# DSO_RAM.net
KiCad netlist of a schematic drawn in Altium Designer
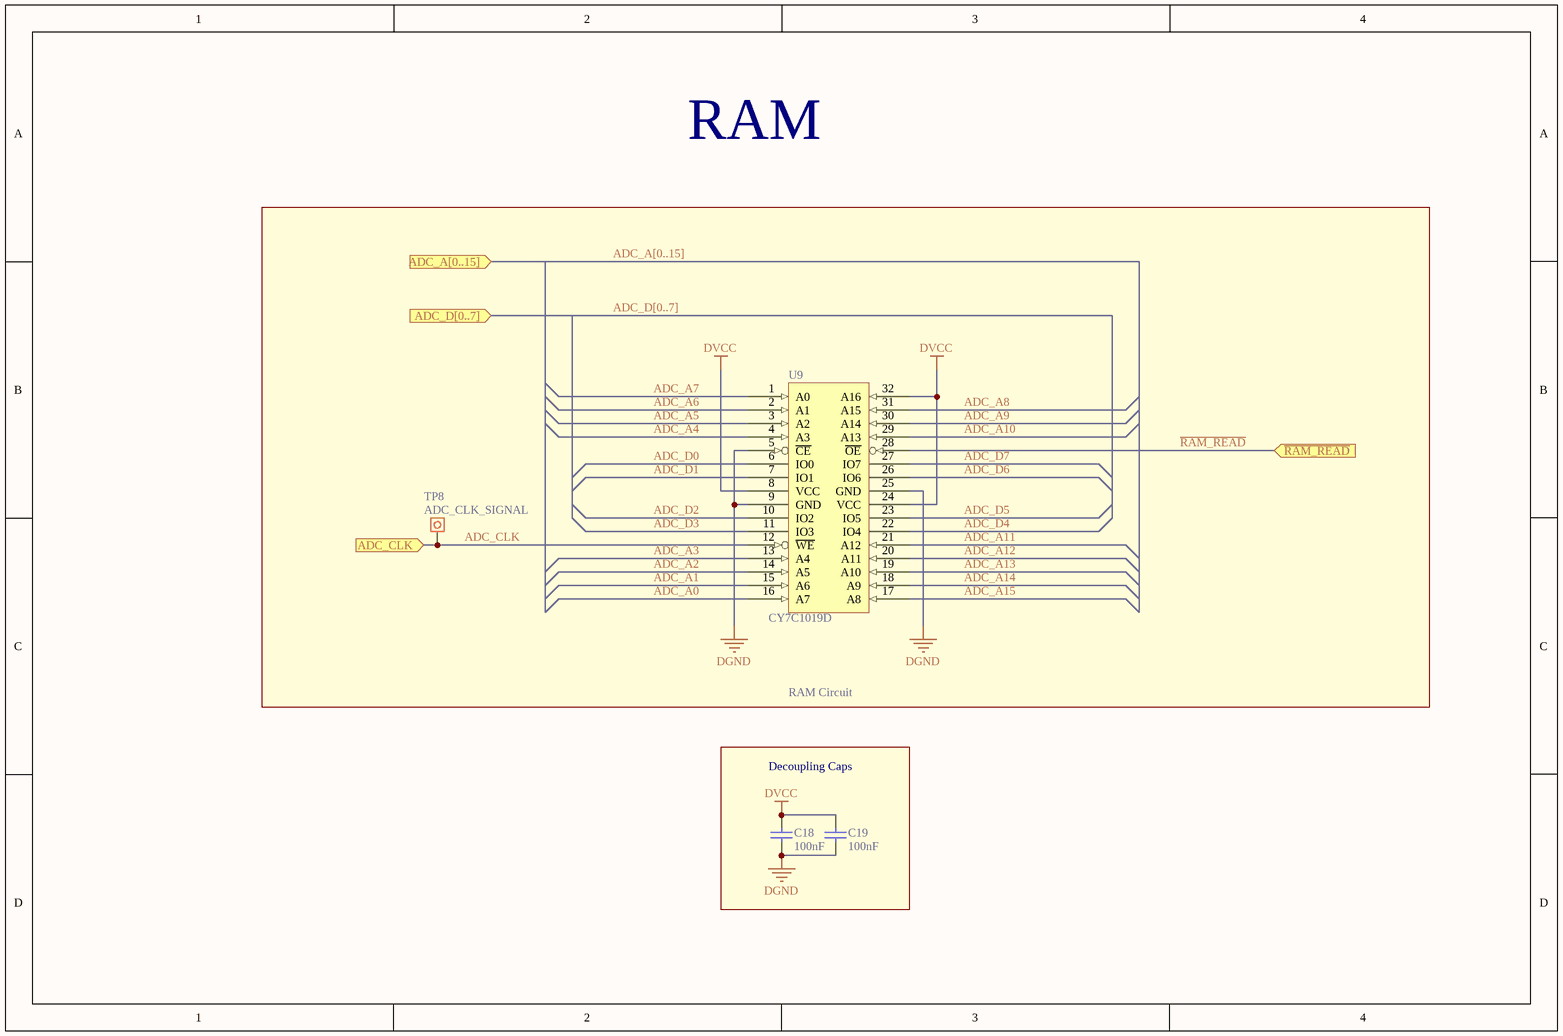
[diagram p0: DSO_RAM.SchDoc]

(export (version "E")
  (design (tool "Eeschema 10.0.6"))
  (components
    (comp (ref "C18")
      (value "100nF")
      (footprint "0805C")
      (description "Capacitor")
      (fields (field (name "REVIEWED BY") "RM - 2018/08/05"))
      (libsource (lib "DSO") (part "C"))
    )
    (comp (ref "C19")
      (value "100nF")
      (footprint "0805C")
      (description "Capacitor")
      (fields (field (name "REVIEWED BY") "RM - 2018/08/05"))
      (libsource (lib "DSO") (part "C"))
    )
    (comp (ref "TP8")
      (value "ADC_CLK_SIGNAL")
      (footprint "Testpoin")
      (description "Pad")
      (fields (field (name "Comment") "INPUT"))
      (libsource (lib "DSO") (part "Test Point"))
    )
    (comp (ref "U9")
      (value "CY7C1019D")
      (footprint "TSOP-32")
      (description "SRAM 128k x 8")
      (fields (field (name "REVIEWED BY") "RM - 2018/08/05"))
      (libsource (lib "DSO") (part "CY7C1019D"))
    )
  )
  (nets
    (net (code "1") (name "/ADC_A0") (class "Default")
      (node (ref "U9") (pin "16") (pinfunction "A7_16") (pintype "input"))
    )
    (net (code "2") (name "/ADC_A1") (class "Default")
      (node (ref "U9") (pin "15") (pinfunction "A6_15") (pintype "input"))
    )
    (net (code "3") (name "/ADC_A2") (class "Default")
      (node (ref "U9") (pin "14") (pinfunction "A5_14") (pintype "input"))
    )
    (net (code "4") (name "/ADC_A3") (class "Default")
      (node (ref "U9") (pin "13") (pinfunction "A4_13") (pintype "input"))
    )
    (net (code "5") (name "/ADC_A4") (class "Default")
      (node (ref "U9") (pin "4") (pinfunction "A3_4") (pintype "input"))
    )
    (net (code "6") (name "/ADC_A5") (class "Default")
      (node (ref "U9") (pin "3") (pinfunction "A2_3") (pintype "input"))
    )
    (net (code "7") (name "/ADC_A6") (class "Default")
      (node (ref "U9") (pin "2") (pinfunction "A1_2") (pintype "input"))
    )
    (net (code "8") (name "/ADC_A7") (class "Default")
      (node (ref "U9") (pin "1") (pinfunction "A0_1") (pintype "input"))
    )
    (net (code "9") (name "/ADC_A8") (class "Default")
      (node (ref "U9") (pin "31") (pinfunction "A15_31") (pintype "input"))
    )
    (net (code "10") (name "/ADC_A9") (class "Default")
      (node (ref "U9") (pin "30") (pinfunction "A14_30") (pintype "input"))
    )
    (net (code "11") (name "/ADC_A10") (class "Default")
      (node (ref "U9") (pin "29") (pinfunction "A13_29") (pintype "input"))
    )
    (net (code "12") (name "/ADC_A11") (class "Default")
      (node (ref "U9") (pin "21") (pinfunction "A12_21") (pintype "input"))
    )
    (net (code "13") (name "/ADC_A12") (class "Default")
      (node (ref "U9") (pin "20") (pinfunction "A11_20") (pintype "input"))
    )
    (net (code "14") (name "/ADC_A13") (class "Default")
      (node (ref "U9") (pin "19") (pinfunction "A10_19") (pintype "input"))
    )
    (net (code "15") (name "/ADC_A14") (class "Default")
      (node (ref "U9") (pin "18") (pinfunction "A9_18") (pintype "input"))
    )
    (net (code "16") (name "/ADC_A15") (class "Default")
      (node (ref "U9") (pin "17") (pinfunction "A8_17") (pintype "input"))
    )
    (net (code "18") (name "/ADC_CLK") (class "Default")
      (node (ref "TP8") (pin "1") (pintype "passive"))
      (node (ref "U9") (pin "12") (pinfunction "~{WE}_12") (pintype "input"))
    )
    (net (code "19") (name "/ADC_D0") (class "Default")
      (node (ref "U9") (pin "6") (pinfunction "IO0_6") (pintype "tri_state"))
    )
    (net (code "20") (name "/ADC_D1") (class "Default")
      (node (ref "U9") (pin "7") (pinfunction "IO1_7") (pintype "tri_state"))
    )
    (net (code "21") (name "/ADC_D2") (class "Default")
      (node (ref "U9") (pin "10") (pinfunction "IO2_10") (pintype "tri_state"))
    )
    (net (code "22") (name "/ADC_D3") (class "Default")
      (node (ref "U9") (pin "11") (pinfunction "IO3_11") (pintype "tri_state"))
    )
    (net (code "23") (name "/ADC_D4") (class "Default")
      (node (ref "U9") (pin "22") (pinfunction "IO4_22") (pintype "tri_state"))
    )
    (net (code "24") (name "/ADC_D5") (class "Default")
      (node (ref "U9") (pin "23") (pinfunction "IO5_23") (pintype "tri_state"))
    )
    (net (code "25") (name "/ADC_D6") (class "Default")
      (node (ref "U9") (pin "26") (pinfunction "IO6_26") (pintype "tri_state"))
    )
    (net (code "26") (name "/ADC_D7") (class "Default")
      (node (ref "U9") (pin "27") (pinfunction "IO7_27") (pintype "tri_state"))
    )
    (net (code "28") (name "/~{RAM_READ}") (class "Default")
      (node (ref "U9") (pin "28") (pinfunction "~{OE}_28") (pintype "input"))
    )
    (net (code "29") (name "DGND") (class "Default")
      (node (ref "C18") (pin "2") (pinfunction "2_2") (pintype "passive"))
      (node (ref "C19") (pin "2") (pinfunction "2_2") (pintype "passive"))
      (node (ref "U9") (pin "25") (pinfunction "GND_25") (pintype "passive"))
      (node (ref "U9") (pin "5") (pinfunction "~{CE}_5") (pintype "input"))
      (node (ref "U9") (pin "9") (pinfunction "GND_9") (pintype "passive"))
    )
    (net (code "30") (name "DVCC") (class "Default")
      (node (ref "C18") (pin "1") (pinfunction "1_1") (pintype "passive"))
      (node (ref "C19") (pin "1") (pinfunction "1_1") (pintype "passive"))
      (node (ref "U9") (pin "24") (pinfunction "VCC_24") (pintype "passive"))
      (node (ref "U9") (pin "32") (pinfunction "A16_32") (pintype "input"))
      (node (ref "U9") (pin "8") (pinfunction "VCC_8") (pintype "passive"))
    )
  )
)
